# projekt.net
KiCad netlist of a schematic drawn in EAGLE
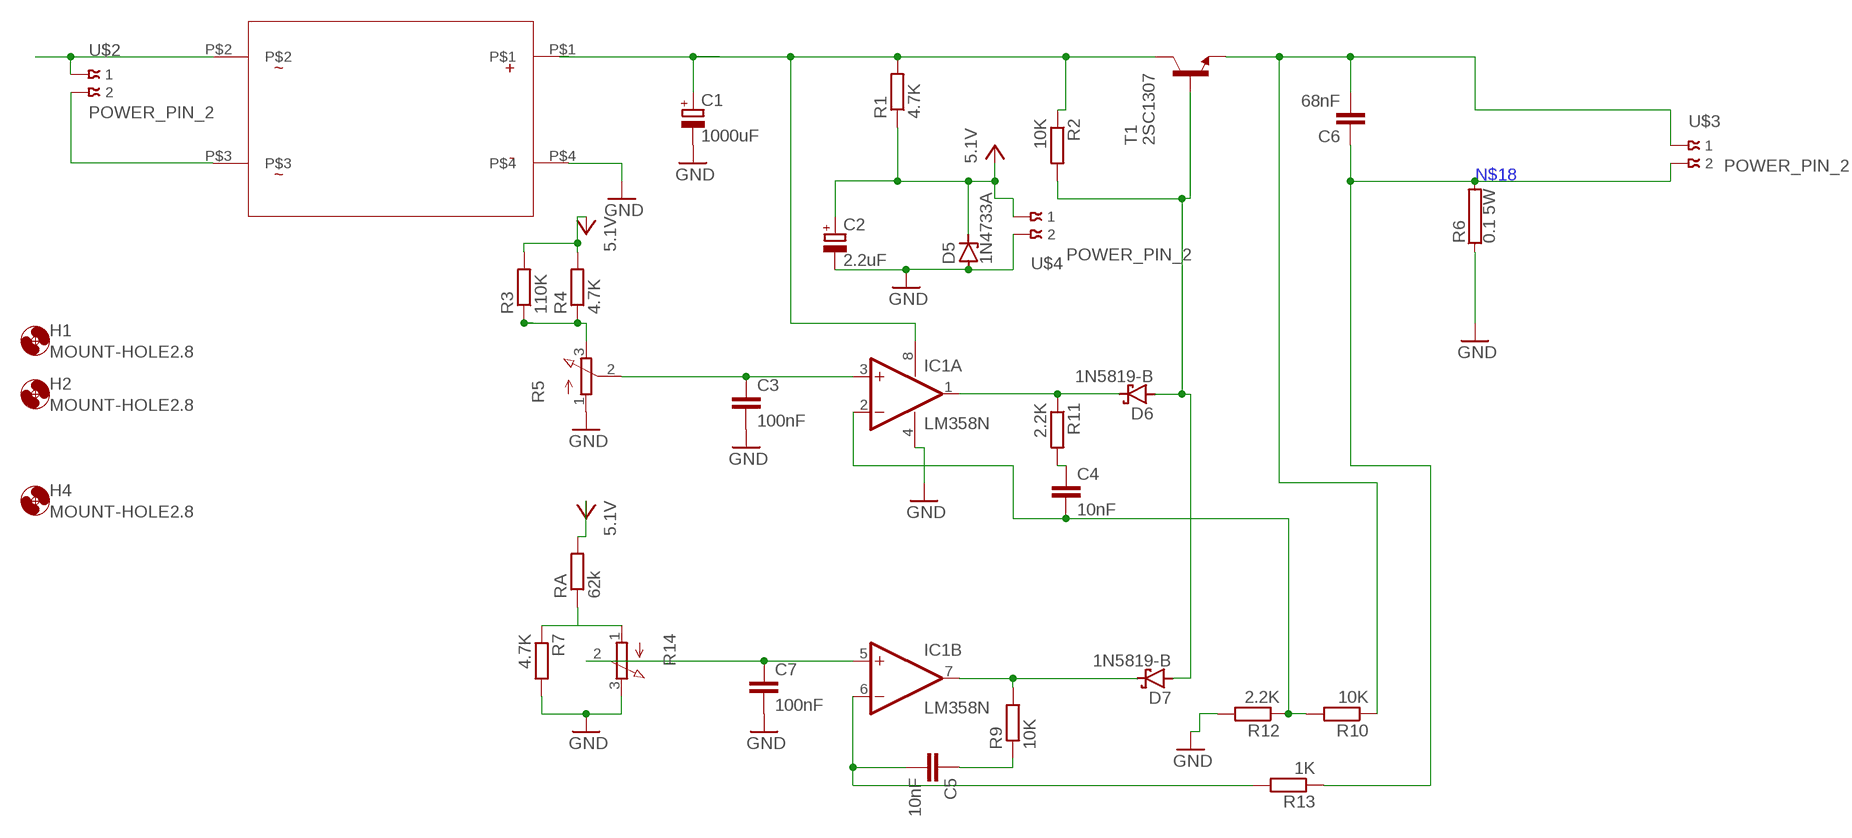
[diagram p0: schematic, sheet 1]

(export (version "E")
  (design (tool "Eeschema 10.0.6"))
  (components
    (comp (ref "C1")
      (value "1000uF")
      (footprint "eagle-import:E7,5-18")
      (libsource (lib "eagle-import") (part "CPOL-EUE7.5-18"))
    )
    (comp (ref "C2")
      (value "2.2uF")
      (footprint "eagle-import:E2,5-6E")
      (libsource (lib "eagle-import") (part "CPOL-EUE2,5-6E"))
    )
    (comp (ref "C3")
      (value "100nF")
      (footprint "eagle-import:C050-025X075")
      (libsource (lib "eagle-import") (part "C-EU050-025X075"))
    )
    (comp (ref "C4")
      (value "10nF")
      (footprint "eagle-import:C050-025X075")
      (libsource (lib "eagle-import") (part "C-EU050-025X075"))
    )
    (comp (ref "C5")
      (value "10nF")
      (footprint "eagle-import:C050-025X075")
      (libsource (lib "eagle-import") (part "C-EU050-025X075"))
    )
    (comp (ref "C6")
      (value "68nF")
      (footprint "eagle-import:C050-025X075")
      (libsource (lib "eagle-import") (part "C-EU050-025X075"))
    )
    (comp (ref "C7")
      (value "100nF")
      (footprint "eagle-import:C050-025X075")
      (libsource (lib "eagle-import") (part "C-EU050-025X075"))
    )
    (comp (ref "D5")
      (value "1N4733A")
      (footprint "eagle-import:DO41Z10")
      (libsource (lib "eagle-import") (part "ZENER-DIODEDO41Z10"))
    )
    (comp (ref "D6")
      (value "1N5819-B")
      (footprint "eagle-import:DO41-7.6")
      (libsource (lib "eagle-import") (part "1N5819-B"))
    )
    (comp (ref "D7")
      (value "1N5819-B")
      (footprint "eagle-import:DO41-7.6")
      (libsource (lib "eagle-import") (part "1N5819-B"))
    )
    (comp (ref "H1")
      (value "MOUNT-HOLE2.8")
      (footprint "eagle-import:2,8")
      (libsource (lib "eagle-import") (part "MOUNT-HOLE2.8"))
    )
    (comp (ref "H2")
      (value "MOUNT-HOLE2.8")
      (footprint "eagle-import:2,8")
      (libsource (lib "eagle-import") (part "MOUNT-HOLE2.8"))
    )
    (comp (ref "H4")
      (value "MOUNT-HOLE2.8")
      (footprint "eagle-import:2,8")
      (libsource (lib "eagle-import") (part "MOUNT-HOLE2.8"))
    )
    (comp (ref "IC1")
      (value "LM358N")
      (footprint "eagle-import:DIL08")
      (libsource (lib "eagle-import") (part "LM358N"))
    )
    (comp (ref "R1")
      (value "4.7K")
      (footprint "eagle-import:0207_10")
      (libsource (lib "eagle-import") (part "R-EU_0207/10"))
    )
    (comp (ref "R2")
      (value "10K")
      (footprint "eagle-import:0207_10")
      (libsource (lib "eagle-import") (part "R-EU_0207/10"))
    )
    (comp (ref "R3")
      (value "110K")
      (footprint "eagle-import:0207_10")
      (libsource (lib "eagle-import") (part "R-EU_0207/10"))
    )
    (comp (ref "R4")
      (value "4.7K")
      (footprint "eagle-import:0207_10")
      (libsource (lib "eagle-import") (part "R-EU_0207/10"))
    )
    (comp (ref "R5")
      (value "3RP/1610N")
      (footprint "eagle-import:3RP_1610N")
      (libsource (lib "eagle-import") (part "3RP/1610N"))
    )
    (comp (ref "R6")
      (value "0.1 5W")
      (footprint "eagle-import:KWP333")
      (libsource (lib "eagle-import") (part "RKWP333"))
    )
    (comp (ref "R7")
      (value "4.7K")
      (footprint "eagle-import:0207_10")
      (libsource (lib "eagle-import") (part "R-EU_0207/10"))
    )
    (comp (ref "R9")
      (value "10K")
      (footprint "eagle-import:0207_10")
      (libsource (lib "eagle-import") (part "R-EU_0207/10"))
    )
    (comp (ref "R10")
      (value "10K")
      (footprint "eagle-import:0207_10")
      (libsource (lib "eagle-import") (part "R-EU_0207/10"))
    )
    (comp (ref "R11")
      (value "2.2K")
      (footprint "eagle-import:0207_10")
      (libsource (lib "eagle-import") (part "R-EU_0207/10"))
    )
    (comp (ref "R12")
      (value "2.2K")
      (footprint "eagle-import:0207_10")
      (libsource (lib "eagle-import") (part "R-EU_0207/10"))
    )
    (comp (ref "R13")
      (value "1K")
      (footprint "eagle-import:0207_10")
      (libsource (lib "eagle-import") (part "R-EU_0207/10"))
    )
    (comp (ref "R14")
      (value "3RP/1610N")
      (footprint "eagle-import:3RP_1610N")
      (libsource (lib "eagle-import") (part "3RP/1610N"))
    )
    (comp (ref "RA")
      (value "62k")
      (footprint "eagle-import:0207_10")
      (libsource (lib "eagle-import") (part "R-EU_0207/10"))
    )
    (comp (ref "T1")
      (value "2SC1307")
      (footprint "eagle-import:TO220AV")
      (libsource (lib "eagle-import") (part "2SC1307"))
    )
    (comp (ref "U$1")
      (value "GBP201-YAN")
      (footprint "eagle-import:GBP201")
      (libsource (lib "eagle-import") (part "GBP201-YAN"))
    )
    (comp (ref "U$2")
      (value "POWER_PIN_2")
      (footprint "eagle-import:PIN2")
      (libsource (lib "eagle-import") (part "POWER_PIN_2"))
    )
    (comp (ref "U$3")
      (value "POWER_PIN_2")
      (footprint "eagle-import:PIN2")
      (libsource (lib "eagle-import") (part "POWER_PIN_2"))
    )
    (comp (ref "U$4")
      (value "POWER_PIN_2")
      (footprint "eagle-import:PIN2")
      (libsource (lib "eagle-import") (part "POWER_PIN_2"))
    )
  )
  (nets
    (net (code "1") (name "5.1V") (class "Default")
      (node (ref "C2") (pin "+") (pinfunction "+_+") (pintype "passive"))
      (node (ref "D5") (pin "C") (pinfunction "C_C") (pintype "passive"))
      (node (ref "R1") (pin "1") (pinfunction "1_1") (pintype "passive"))
      (node (ref "R3") (pin "2") (pinfunction "2_2") (pintype "passive"))
      (node (ref "R4") (pin "2") (pinfunction "2_2") (pintype "passive"))
      (node (ref "RA") (pin "2") (pinfunction "2_2") (pintype "passive"))
      (node (ref "U$4") (pin "P$1") (pinfunction "1_P$1") (pintype "passive"))
    )
    (net (code "2") (name "GND") (class "Default")
      (node (ref "C1") (pin "-") (pinfunction "-_-") (pintype "passive"))
      (node (ref "C2") (pin "-") (pinfunction "-_-") (pintype "passive"))
      (node (ref "C3") (pin "2") (pinfunction "2_2") (pintype "passive"))
      (node (ref "C7") (pin "2") (pinfunction "2_2") (pintype "passive"))
      (node (ref "D5") (pin "A") (pinfunction "A_A") (pintype "passive"))
      (node (ref "IC1") (pin "4") (pinfunction "V-_4") (pintype "power_in"))
      (node (ref "R12") (pin "2") (pinfunction "2_2") (pintype "passive"))
      (node (ref "R14") (pin "3") (pinfunction "E_3") (pintype "passive"))
      (node (ref "R5") (pin "1") (pinfunction "A_1") (pintype "passive"))
      (node (ref "R6") (pin "1") (pinfunction "1_1") (pintype "passive"))
      (node (ref "R7") (pin "2") (pinfunction "2_2") (pintype "passive"))
      (node (ref "U$1") (pin "P$4") (pinfunction "P$4_P$4") (pintype "bidirectional"))
      (node (ref "U$4") (pin "P$2") (pinfunction "2_P$2") (pintype "passive"))
    )
    (net (code "3") (name "Net-(C4-Pad1)") (class "Default")
      (node (ref "C4") (pin "1") (pinfunction "1_1") (pintype "passive"))
      (node (ref "R11") (pin "2") (pinfunction "2_2") (pintype "passive"))
    )
    (net (code "4") (name "Net-(C5-Pad1)") (class "Default")
      (node (ref "C5") (pin "1") (pinfunction "1_1") (pintype "passive"))
      (node (ref "R9") (pin "1") (pinfunction "1_1") (pintype "passive"))
    )
    (net (code "5") (name "Net-(IC1A-+IN)") (class "Default")
      (node (ref "C3") (pin "1") (pinfunction "1_1") (pintype "passive"))
      (node (ref "IC1") (pin "3") (pinfunction "+IN_3") (pintype "input"))
      (node (ref "R5") (pin "2") (pinfunction "S_2") (pintype "passive"))
    )
    (net (code "6") (name "Net-(IC1A--IN)") (class "Default")
      (node (ref "C4") (pin "2") (pinfunction "2_2") (pintype "passive"))
      (node (ref "IC1") (pin "2") (pinfunction "-IN_2") (pintype "input"))
      (node (ref "R10") (pin "2") (pinfunction "2_2") (pintype "passive"))
      (node (ref "R12") (pin "1") (pinfunction "1_1") (pintype "passive"))
    )
    (net (code "7") (name "Net-(IC1A-OUT)") (class "Default")
      (node (ref "D6") (pin "C") (pinfunction "C_C") (pintype "passive"))
      (node (ref "IC1") (pin "1") (pinfunction "OUT_1") (pintype "output"))
      (node (ref "R11") (pin "1") (pinfunction "1_1") (pintype "passive"))
    )
    (net (code "8") (name "Net-(IC1B-+IN)") (class "Default")
      (node (ref "C7") (pin "1") (pinfunction "1_1") (pintype "passive"))
      (node (ref "IC1") (pin "5") (pinfunction "+IN_5") (pintype "input"))
      (node (ref "R14") (pin "2") (pinfunction "S_2") (pintype "passive"))
    )
    (net (code "9") (name "Net-(IC1B--IN)") (class "Default")
      (node (ref "C5") (pin "2") (pinfunction "2_2") (pintype "passive"))
      (node (ref "IC1") (pin "6") (pinfunction "-IN_6") (pintype "input"))
      (node (ref "R13") (pin "2") (pinfunction "2_2") (pintype "passive"))
    )
    (net (code "10") (name "Net-(IC1B-OUT)") (class "Default")
      (node (ref "D7") (pin "C") (pinfunction "C_C") (pintype "passive"))
      (node (ref "IC1") (pin "7") (pinfunction "OUT_7") (pintype "output"))
      (node (ref "R9") (pin "2") (pinfunction "2_2") (pintype "passive"))
    )
    (net (code "11") (name "Net-(IC1C-V+)") (class "Default")
      (node (ref "C1") (pin "+") (pinfunction "+_+") (pintype "passive"))
      (node (ref "IC1") (pin "8") (pinfunction "V+_8") (pintype "power_in"))
      (node (ref "R1") (pin "2") (pinfunction "2_2") (pintype "passive"))
      (node (ref "R2") (pin "1") (pinfunction "1_1") (pintype "passive"))
      (node (ref "T1") (pin "2") (pinfunction "C_2") (pintype "passive"))
      (node (ref "U$1") (pin "P$1") (pinfunction "P$1_P$1") (pintype "bidirectional"))
    )
    (net (code "12") (name "Net-(R5-E)") (class "Default")
      (node (ref "R3") (pin "1") (pinfunction "1_1") (pintype "passive"))
      (node (ref "R4") (pin "1") (pinfunction "1_1") (pintype "passive"))
      (node (ref "R5") (pin "3") (pinfunction "E_3") (pintype "passive"))
    )
    (net (code "13") (name "Net-(R14-A)") (class "Default")
      (node (ref "R14") (pin "1") (pinfunction "A_1") (pintype "passive"))
      (node (ref "R7") (pin "1") (pinfunction "1_1") (pintype "passive"))
      (node (ref "RA") (pin "1") (pinfunction "1_1") (pintype "passive"))
    )
    (net (code "14") (name "Net-(T1-B)") (class "Default")
      (node (ref "D6") (pin "A") (pinfunction "A_A") (pintype "passive"))
      (node (ref "D7") (pin "A") (pinfunction "A_A") (pintype "passive"))
      (node (ref "R2") (pin "2") (pinfunction "2_2") (pintype "passive"))
      (node (ref "T1") (pin "1") (pinfunction "B_1") (pintype "passive"))
    )
    (net (code "15") (name "Net-(T1-E)") (class "Default")
      (node (ref "C6") (pin "2") (pinfunction "2_2") (pintype "passive"))
      (node (ref "R10") (pin "1") (pinfunction "1_1") (pintype "passive"))
      (node (ref "T1") (pin "3") (pinfunction "E_3") (pintype "passive"))
      (node (ref "U$3") (pin "P$1") (pinfunction "1_P$1") (pintype "passive"))
    )
    (net (code "16") (name "Net-(U$2-1)") (class "Default")
      (node (ref "U$1") (pin "P$2") (pinfunction "P$2_P$2") (pintype "bidirectional"))
      (node (ref "U$2") (pin "P$1") (pinfunction "1_P$1") (pintype "passive"))
    )
    (net (code "17") (name "Net-(U$2-2)") (class "Default")
      (node (ref "U$1") (pin "P$3") (pinfunction "P$3_P$3") (pintype "bidirectional"))
      (node (ref "U$2") (pin "P$2") (pinfunction "2_P$2") (pintype "passive"))
    )
    (net (code "18") (name "Net-(U$3-2)") (class "Default")
      (node (ref "C6") (pin "1") (pinfunction "1_1") (pintype "passive"))
      (node (ref "R13") (pin "1") (pinfunction "1_1") (pintype "passive"))
      (node (ref "R6") (pin "2") (pinfunction "2_2") (pintype "passive"))
      (node (ref "U$3") (pin "P$2") (pinfunction "2_P$2") (pintype "passive"))
    )
  )
)
